# Controller.net
KiCad netlist of a schematic drawn in Altium Designer
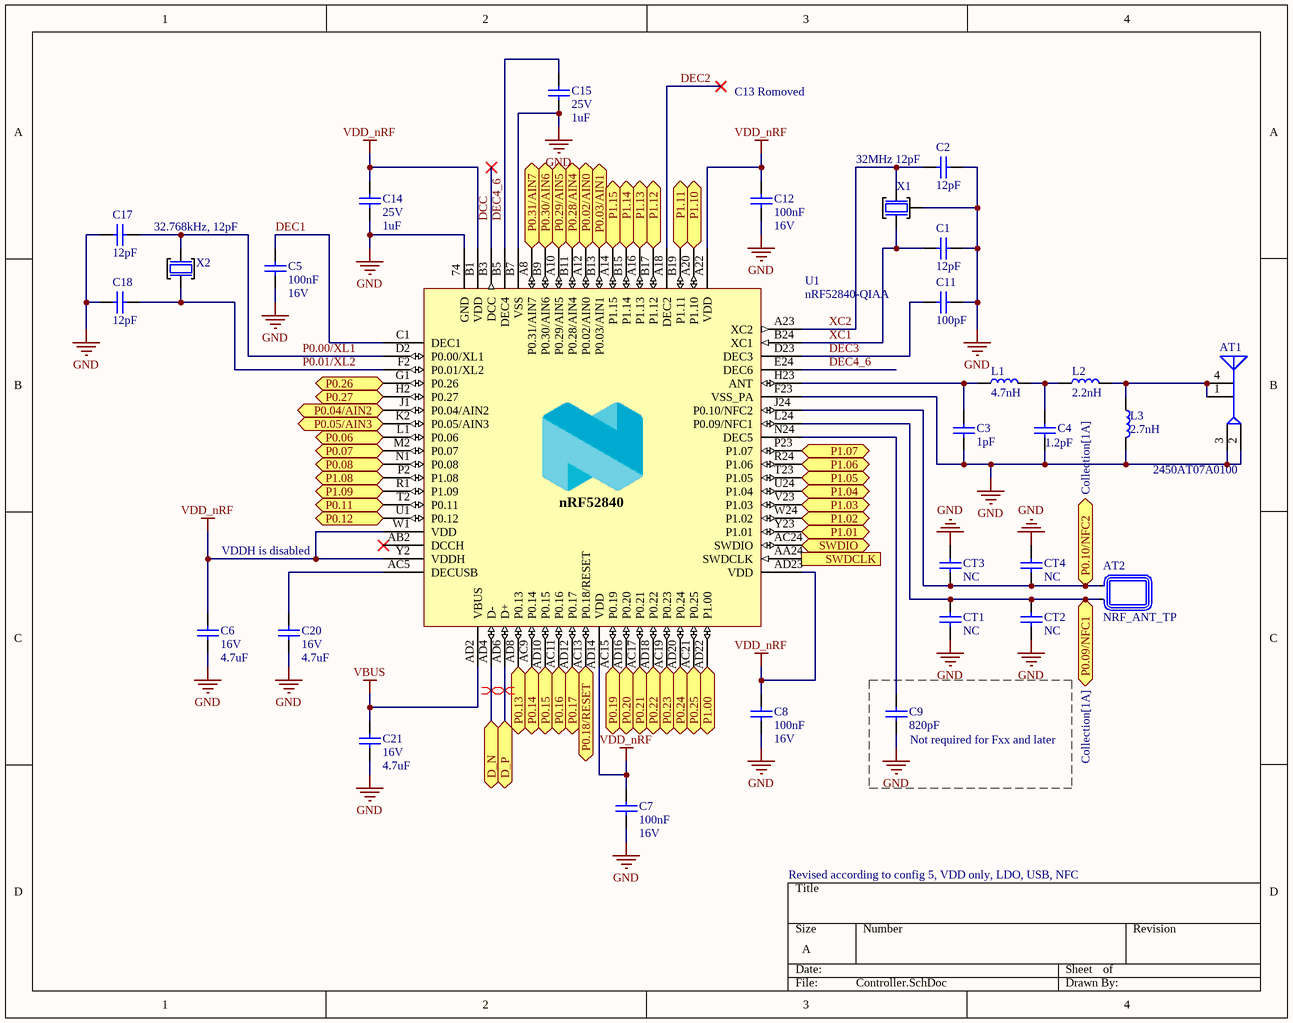
[diagram p0: Controller.SchDoc]

(export (version "E")
  (design (tool "Eeschema 10.0.6"))
  (components
    (comp (ref "AT1")
      (value "2450AT07A0100")
      (footprint "2450AT07A0100-Footprint-1")
      (description "2.4GHz Chip RF Antenna 2.4GHz ~ 2.5GHz 1dBi Solder Surface Mount")
      (libsource (lib "Kirks") (part "2450AT07A0100-Symbol-1"))
    )
    (comp (ref "AT2")
      (value "NRF_ANT_TP")
      (footprint "NRF_ANT_TP-Footprint-1")
      (description "NRF Antenna Testpoint")
      (libsource (lib "Kirks") (part "NRF_ANT_TP-Symbol-1"))
    )
    (comp (ref "C1")
      (value "12pF")
      (footprint "0402_C")
      (description "Chip Capacitor")
      (fields (field (name "VOLTAGE") "50V") (field (name "Comment") "12pF (120) 5% 50V"))
      (libsource (lib "LocalLib") (part "0402 12pF (120) 5% 50V"))
    )
    (comp (ref "C2")
      (value "12pF")
      (footprint "0402_C")
      (description "Chip Capacitor")
      (fields (field (name "VOLTAGE") "50V") (field (name "Comment") "12pF (120) 5% 50V"))
      (libsource (lib "LocalLib") (part "0402 12pF (120) 5% 50V"))
    )
    (comp (ref "C3")
      (value "1pF")
      (footprint "0402_C")
      (description "Chip Capacitor")
      (fields (field (name "VOLTAGE") "50V") (field (name "Comment") "1pF (1R0) 0.25pF 50V"))
      (libsource (lib "LocalLib") (part "0402 1pF (1R0) 0.25pF 50V"))
    )
    (comp (ref "C4")
      (value "1.2pF")
      (footprint "0402_C")
      (description "Chip Capacitor")
      (fields (field (name "VOLTAGE") "50V") (field (name "Comment") "1.2pF (1R2) 50V"))
      (libsource (lib "LocalLib") (part "0402 1.2pF (1R2) 50V"))
    )
    (comp (ref "C5")
      (value "100nF")
      (footprint "0402_C")
      (description "Chip Capacitor")
      (fields (field (name "VOLTAGE") "16V") (field (name "Comment") "100nF (104) 10% 16V"))
      (libsource (lib "LocalLib") (part "0402 100nF (104) 10% 16V"))
    )
    (comp (ref "C6")
      (value "4.7uF")
      (footprint "0603_C")
      (description "Chip Capacitor")
      (fields (field (name "VOLTAGE") "16V") (field (name "Comment") "4.7uF (475) 10% 16V"))
      (libsource (lib "LocalLib") (part "0603 4.7uF (475) 10% 16V"))
    )
    (comp (ref "C7")
      (value "100nF")
      (footprint "0402_C")
      (description "Chip Capacitor")
      (fields (field (name "VOLTAGE") "16V") (field (name "Comment") "100nF (104) 10% 16V"))
      (libsource (lib "LocalLib") (part "0402 100nF (104) 10% 16V"))
    )
    (comp (ref "C8")
      (value "100nF")
      (footprint "0402_C")
      (description "Chip Capacitor")
      (fields (field (name "VOLTAGE") "16V") (field (name "Comment") "100nF (104) 10% 16V"))
      (libsource (lib "LocalLib") (part "0402 100nF (104) 10% 16V"))
    )
    (comp (ref "C9")
      (value "820pF")
      (footprint "0402_C")
      (description "Chip Capacitor")
      (fields (field (name "VOLTAGE") "50V") (field (name "Comment") "820pF (821) 10% 50V"))
      (libsource (lib "LocalLib") (part "0402 820pF (821) 10% 50V"))
    )
    (comp (ref "C11")
      (value "100pF")
      (footprint "0402_C")
      (description "Chip Capacitor")
      (fields (field (name "VOLTAGE") "50V") (field (name "Comment") "100pF (101) 5% 50V"))
      (libsource (lib "LocalLib") (part "0402 100pF (101) 5% 50V"))
    )
    (comp (ref "C12")
      (value "100nF")
      (footprint "0402_C")
      (description "Chip Capacitor")
      (fields (field (name "VOLTAGE") "16V") (field (name "Comment") "100nF (104) 10% 16V"))
      (libsource (lib "LocalLib") (part "0402 100nF (104) 10% 16V"))
    )
    (comp (ref "C14")
      (value "1uF")
      (footprint "0402_C")
      (description "Chip Capacitor")
      (fields (field (name "VOLTAGE") "25V") (field (name "Comment") "1uF (105) 10% 25V"))
      (libsource (lib "LocalLib") (part "0402 1uF (105) 10% 25V"))
    )
    (comp (ref "C15")
      (value "1uF")
      (footprint "0402_C")
      (description "Chip Capacitor")
      (fields (field (name "VOLTAGE") "25V") (field (name "Comment") "1uF (105) 10% 25V"))
      (libsource (lib "LocalLib") (part "0402 1uF (105) 10% 25V"))
    )
    (comp (ref "C17")
      (value "12pF")
      (footprint "0402_C")
      (description "Chip Capacitor")
      (fields (field (name "VOLTAGE") "50V") (field (name "Comment") "12pF (120) 5% 50V"))
      (libsource (lib "LocalLib") (part "0402 12pF (120) 5% 50V"))
    )
    (comp (ref "C18")
      (value "12pF")
      (footprint "0402_C")
      (description "Chip Capacitor")
      (fields (field (name "VOLTAGE") "50V") (field (name "Comment") "12pF (120) 5% 50V"))
      (libsource (lib "LocalLib") (part "0402 12pF (120) 5% 50V"))
    )
    (comp (ref "C20")
      (value "4.7uF")
      (footprint "0603_C")
      (description "Chip Capacitor")
      (fields (field (name "VOLTAGE") "16V") (field (name "Comment") "4.7uF (475) 10% 16V"))
      (libsource (lib "LocalLib") (part "0603 4.7uF (475) 10% 16V"))
    )
    (comp (ref "C21")
      (value "4.7uF")
      (footprint "0603_C")
      (description "Chip Capacitor")
      (fields (field (name "VOLTAGE") "16V") (field (name "Comment") "4.7uF (475) 10% 16V"))
      (libsource (lib "LocalLib") (part "0603 4.7uF (475) 10% 16V"))
    )
    (comp (ref "CT1")
      (value "NC")
      (footprint "0402_C")
      (description "Chip Capacitor Testpoint")
      (libsource (lib "LocalLib") (part "0402 Capacitor Testpoint"))
    )
    (comp (ref "CT2")
      (value "NC")
      (footprint "0402_C")
      (description "Chip Capacitor Testpoint")
      (libsource (lib "LocalLib") (part "0402 Capacitor Testpoint"))
    )
    (comp (ref "CT3")
      (value "NC")
      (footprint "0402_C")
      (description "Chip Capacitor Testpoint")
      (libsource (lib "LocalLib") (part "0402 Capacitor Testpoint"))
    )
    (comp (ref "CT4")
      (value "NC")
      (footprint "0402_C")
      (description "Chip Capacitor Testpoint")
      (libsource (lib "LocalLib") (part "0402 Capacitor Testpoint"))
    )
    (comp (ref "L1")
      (value "4.7nH")
      (footprint "0402_L")
      (description "Chip Inductor")
      (libsource (lib "LocalLib") (part "0402 4.7nH 0.3nH"))
    )
    (comp (ref "L2")
      (value "2.2nH")
      (footprint "0402_L")
      (description "Chip Inductor")
      (libsource (lib "LocalLib") (part "0402 2.2nH"))
    )
    (comp (ref "L3")
      (value "2.7nH")
      (footprint "0402_L")
      (description "Chip Inductor")
      (libsource (lib "LocalLib") (part "0402 2.7nH 0.3nH"))
    )
    (comp (ref "U1")
      (value "nRF52840-QIAA")
      (footprint "AQFN50P700X700X85_HS-74N")
      (description "Multi-protocol Bluetooth Low Energy, IEEE 802.15.4, ANT and 2.4GHz proprietary system-on-chip")
      (libsource (lib "LocalLib") (part "nRF52840-QIAA"))
    )
    (comp (ref "X1")
      (value "32MHz 12pF")
      (footprint "XTAL_2016_4P")
      (description "XTAL SMD 2016, 32MHz, Cl=12pF, Total Tol: ±20ppm")
      (libsource (lib "LocalLib") (part "XTAL_SMD2016_32MHz_12pF"))
    )
    (comp (ref "X2")
      (value "32.768kHz, 12pF")
      (footprint "XTAL_2012_2P")
      (description "32.768kHz 12pF ±20ppm SMD2012-2P  Crystals ROHS")
      (libsource (lib "LocalLib") (part "XTAL_SMD2012_32.768kHz_12pF"))
    )
  )
  (nets
    (net (code "1") (name "/DCC") (class "Default")
      (node (ref "U1") (pin "B3") (pinfunction "DCC_B3") (pintype "output+no_connect"))
    )
    (net (code "2") (name "/DEC1") (class "Default")
      (node (ref "C5") (pin "2") (pinfunction "2_2") (pintype "passive"))
      (node (ref "U1") (pin "C1") (pinfunction "DEC1_C1") (pintype "power_in"))
    )
    (net (code "3") (name "/DEC2") (class "Default")
      (node (ref "U1") (pin "A18") (pinfunction "DEC2_A18") (pintype "power_in+no_connect"))
    )
    (net (code "4") (name "/DEC3") (class "Default")
      (node (ref "C11") (pin "1") (pinfunction "1_1") (pintype "passive"))
      (node (ref "U1") (pin "D23") (pinfunction "DEC3_D23") (pintype "power_in"))
    )
    (net (code "5") (name "/DEC4_6") (class "Default")
      (node (ref "C15") (pin "2") (pinfunction "2_2") (pintype "passive"))
      (node (ref "U1") (pin "B5") (pinfunction "DEC4_B5") (pintype "power_in"))
      (node (ref "U1") (pin "E24") (pinfunction "DEC6_E24") (pintype "power_in"))
    )
    (net (code "6") (name "/D_N") (class "Default")
      (node (ref "U1") (pin "AD4") (pinfunction "D-_AD4") (pintype "bidirectional"))
    )
    (net (code "7") (name "/D_P") (class "Default")
      (node (ref "U1") (pin "AD6") (pinfunction "D+_AD6") (pintype "bidirectional"))
    )
    (net (code "8") (name "/P0.00{slash}XL1") (class "Default")
      (node (ref "C17") (pin "2") (pinfunction "2_2") (pintype "passive"))
      (node (ref "U1") (pin "D2") (pinfunction "P0.00/XL1_D2") (pintype "bidirectional"))
      (node (ref "X2") (pin "2") (pinfunction "OUT_2") (pintype "passive"))
    )
    (net (code "9") (name "/P0.01{slash}XL2") (class "Default")
      (node (ref "C18") (pin "2") (pinfunction "2_2") (pintype "passive"))
      (node (ref "U1") (pin "F2") (pinfunction "P0.01/XL2_F2") (pintype "bidirectional"))
      (node (ref "X2") (pin "1") (pinfunction "IN_1") (pintype "passive"))
    )
    (net (code "10") (name "/P0.02{slash}AIN0") (class "Default")
      (node (ref "U1") (pin "A12") (pinfunction "P0.02/AIN0_A12") (pintype "bidirectional"))
    )
    (net (code "11") (name "/P0.03{slash}AIN1") (class "Default")
      (node (ref "U1") (pin "B13") (pinfunction "P0.03/AIN1_B13") (pintype "bidirectional"))
    )
    (net (code "12") (name "/P0.04{slash}AIN2") (class "Default")
      (node (ref "U1") (pin "J1") (pinfunction "P0.04/AIN2_J1") (pintype "bidirectional"))
    )
    (net (code "13") (name "/P0.05{slash}AIN3") (class "Default")
      (node (ref "U1") (pin "K2") (pinfunction "P0.05/AIN3_K2") (pintype "bidirectional"))
    )
    (net (code "14") (name "/P0.06") (class "Default")
      (node (ref "U1") (pin "L1") (pinfunction "P0.06_L1") (pintype "bidirectional"))
    )
    (net (code "15") (name "/P0.07") (class "Default")
      (node (ref "U1") (pin "M2") (pinfunction "P0.07_M2") (pintype "bidirectional"))
    )
    (net (code "16") (name "/P0.08") (class "Default")
      (node (ref "U1") (pin "N1") (pinfunction "P0.08_N1") (pintype "bidirectional"))
    )
    (net (code "17") (name "/P0.09{slash}NFC1") (class "Default")
      (node (ref "AT2") (pin "2") (pinfunction "2_2") (pintype "passive"))
      (node (ref "CT1") (pin "2") (pinfunction "2_2") (pintype "passive"))
      (node (ref "CT2") (pin "2") (pinfunction "2_2") (pintype "passive"))
      (node (ref "U1") (pin "L24") (pinfunction "P0.09/NFC1_L24") (pintype "bidirectional"))
    )
    (net (code "18") (name "/P0.10{slash}NFC2") (class "Default")
      (node (ref "AT2") (pin "1") (pinfunction "1_1") (pintype "passive"))
      (node (ref "CT3") (pin "1") (pinfunction "1_1") (pintype "passive"))
      (node (ref "CT4") (pin "1") (pinfunction "1_1") (pintype "passive"))
      (node (ref "U1") (pin "J24") (pinfunction "P0.10/NFC2_J24") (pintype "bidirectional"))
    )
    (net (code "19") (name "/P0.11") (class "Default")
      (node (ref "U1") (pin "T2") (pinfunction "P0.11_T2") (pintype "bidirectional"))
    )
    (net (code "20") (name "/P0.12") (class "Default")
      (node (ref "U1") (pin "U1") (pinfunction "P0.12_U1") (pintype "bidirectional"))
    )
    (net (code "21") (name "/P0.13") (class "Default")
      (node (ref "U1") (pin "AD8") (pinfunction "P0.13_AD8") (pintype "bidirectional"))
    )
    (net (code "22") (name "/P0.14") (class "Default")
      (node (ref "U1") (pin "AC9") (pinfunction "P0.14_AC9") (pintype "bidirectional"))
    )
    (net (code "23") (name "/P0.15") (class "Default")
      (node (ref "U1") (pin "AD10") (pinfunction "P0.15_AD10") (pintype "bidirectional"))
    )
    (net (code "24") (name "/P0.16") (class "Default")
      (node (ref "U1") (pin "AC11") (pinfunction "P0.16_AC11") (pintype "bidirectional"))
    )
    (net (code "25") (name "/P0.17") (class "Default")
      (node (ref "U1") (pin "AD12") (pinfunction "P0.17_AD12") (pintype "bidirectional"))
    )
    (net (code "26") (name "/P0.18{slash}RESET") (class "Default")
      (node (ref "U1") (pin "AC13") (pinfunction "P0.18/RESET_AC13") (pintype "bidirectional"))
    )
    (net (code "27") (name "/P0.19") (class "Default")
      (node (ref "U1") (pin "AC15") (pinfunction "P0.19_AC15") (pintype "bidirectional"))
    )
    (net (code "28") (name "/P0.20") (class "Default")
      (node (ref "U1") (pin "AD16") (pinfunction "P0.20_AD16") (pintype "bidirectional"))
    )
    (net (code "29") (name "/P0.21") (class "Default")
      (node (ref "U1") (pin "AC17") (pinfunction "P0.21_AC17") (pintype "bidirectional"))
    )
    (net (code "30") (name "/P0.22") (class "Default")
      (node (ref "U1") (pin "AD18") (pinfunction "P0.22_AD18") (pintype "bidirectional"))
    )
    (net (code "31") (name "/P0.23") (class "Default")
      (node (ref "U1") (pin "AC19") (pinfunction "P0.23_AC19") (pintype "bidirectional"))
    )
    (net (code "32") (name "/P0.24") (class "Default")
      (node (ref "U1") (pin "AD20") (pinfunction "P0.24_AD20") (pintype "bidirectional"))
    )
    (net (code "33") (name "/P0.25") (class "Default")
      (node (ref "U1") (pin "AC21") (pinfunction "P0.25_AC21") (pintype "bidirectional"))
    )
    (net (code "34") (name "/P0.26") (class "Default")
      (node (ref "U1") (pin "G1") (pinfunction "P0.26_G1") (pintype "bidirectional"))
    )
    (net (code "35") (name "/P0.27") (class "Default")
      (node (ref "U1") (pin "H2") (pinfunction "P0.27_H2") (pintype "bidirectional"))
    )
    (net (code "36") (name "/P0.28{slash}AIN4") (class "Default")
      (node (ref "U1") (pin "B11") (pinfunction "P0.28/AIN4_B11") (pintype "bidirectional"))
    )
    (net (code "37") (name "/P0.29{slash}AIN5") (class "Default")
      (node (ref "U1") (pin "A10") (pinfunction "P0.29/AIN5_A10") (pintype "bidirectional"))
    )
    (net (code "38") (name "/P0.30{slash}AIN6") (class "Default")
      (node (ref "U1") (pin "B9") (pinfunction "P0.30/AIN6_B9") (pintype "bidirectional"))
    )
    (net (code "39") (name "/P0.31{slash}AIN7") (class "Default")
      (node (ref "U1") (pin "A8") (pinfunction "P0.31/AIN7_A8") (pintype "bidirectional"))
    )
    (net (code "40") (name "/P1.00") (class "Default")
      (node (ref "U1") (pin "AD22") (pinfunction "P1.00_AD22") (pintype "bidirectional"))
    )
    (net (code "41") (name "/P1.01") (class "Default")
      (node (ref "U1") (pin "Y23") (pinfunction "P1.01_Y23") (pintype "bidirectional"))
    )
    (net (code "42") (name "/P1.02") (class "Default")
      (node (ref "U1") (pin "W24") (pinfunction "P1.02_W24") (pintype "bidirectional"))
    )
    (net (code "43") (name "/P1.03") (class "Default")
      (node (ref "U1") (pin "V23") (pinfunction "P1.03_V23") (pintype "bidirectional"))
    )
    (net (code "44") (name "/P1.04") (class "Default")
      (node (ref "U1") (pin "U24") (pinfunction "P1.04_U24") (pintype "bidirectional"))
    )
    (net (code "45") (name "/P1.05") (class "Default")
      (node (ref "U1") (pin "T23") (pinfunction "P1.05_T23") (pintype "bidirectional"))
    )
    (net (code "46") (name "/P1.06") (class "Default")
      (node (ref "U1") (pin "R24") (pinfunction "P1.06_R24") (pintype "bidirectional"))
    )
    (net (code "47") (name "/P1.07") (class "Default")
      (node (ref "U1") (pin "P23") (pinfunction "P1.07_P23") (pintype "bidirectional"))
    )
    (net (code "48") (name "/P1.08") (class "Default")
      (node (ref "U1") (pin "P2") (pinfunction "P1.08_P2") (pintype "bidirectional"))
    )
    (net (code "49") (name "/P1.09") (class "Default")
      (node (ref "U1") (pin "R1") (pinfunction "P1.09_R1") (pintype "bidirectional"))
    )
    (net (code "50") (name "/P1.10") (class "Default")
      (node (ref "U1") (pin "A20") (pinfunction "P1.10_A20") (pintype "bidirectional"))
    )
    (net (code "51") (name "/P1.11") (class "Default")
      (node (ref "U1") (pin "B19") (pinfunction "P1.11_B19") (pintype "bidirectional"))
    )
    (net (code "52") (name "/P1.12") (class "Default")
      (node (ref "U1") (pin "B17") (pinfunction "P1.12_B17") (pintype "bidirectional"))
    )
    (net (code "53") (name "/P1.13") (class "Default")
      (node (ref "U1") (pin "A16") (pinfunction "P1.13_A16") (pintype "bidirectional"))
    )
    (net (code "54") (name "/P1.14") (class "Default")
      (node (ref "U1") (pin "B15") (pinfunction "P1.14_B15") (pintype "bidirectional"))
    )
    (net (code "55") (name "/P1.15") (class "Default")
      (node (ref "U1") (pin "A14") (pinfunction "P1.15_A14") (pintype "bidirectional"))
    )
    (net (code "56") (name "/SWDCLK") (class "Default")
      (node (ref "U1") (pin "AA24") (pinfunction "SWDCLK_AA24") (pintype "input"))
    )
    (net (code "57") (name "/SWDIO") (class "Default")
      (node (ref "U1") (pin "AC24") (pinfunction "SWDIO_AC24") (pintype "bidirectional"))
    )
    (net (code "58") (name "/XC1") (class "Default")
      (node (ref "C1") (pin "1") (pinfunction "1_1") (pintype "passive"))
      (node (ref "U1") (pin "B24") (pinfunction "XC1_B24") (pintype "input"))
      (node (ref "X1") (pin "1") (pinfunction "IN_1") (pintype "passive"))
    )
    (net (code "59") (name "/XC2") (class "Default")
      (node (ref "C2") (pin "1") (pinfunction "1_1") (pintype "passive"))
      (node (ref "U1") (pin "A23") (pinfunction "XC2_A23") (pintype "output"))
      (node (ref "X1") (pin "3") (pinfunction "OUT_3") (pintype "passive"))
    )
    (net (code "60") (name "GND") (class "Default")
      (node (ref "AT1") (pin "2") (pinfunction "2_2") (pintype "passive"))
      (node (ref "AT1") (pin "3") (pinfunction "3_3") (pintype "passive"))
      (node (ref "C1") (pin "2") (pinfunction "2_2") (pintype "passive"))
      (node (ref "C11") (pin "2") (pinfunction "2_2") (pintype "passive"))
      (node (ref "C12") (pin "1") (pinfunction "1_1") (pintype "passive"))
      (node (ref "C14") (pin "1") (pinfunction "1_1") (pintype "passive"))
      (node (ref "C15") (pin "1") (pinfunction "1_1") (pintype "passive"))
      (node (ref "C17") (pin "1") (pinfunction "1_1") (pintype "passive"))
      (node (ref "C18") (pin "1") (pinfunction "1_1") (pintype "passive"))
      (node (ref "C2") (pin "2") (pinfunction "2_2") (pintype "passive"))
      (node (ref "C20") (pin "1") (pinfunction "1_1") (pintype "passive"))
      (node (ref "C21") (pin "1") (pinfunction "1_1") (pintype "passive"))
      (node (ref "C3") (pin "1") (pinfunction "1_1") (pintype "passive"))
      (node (ref "C4") (pin "1") (pinfunction "1_1") (pintype "passive"))
      (node (ref "C5") (pin "1") (pinfunction "1_1") (pintype "passive"))
      (node (ref "C6") (pin "1") (pinfunction "1_1") (pintype "passive"))
      (node (ref "C7") (pin "1") (pinfunction "1_1") (pintype "passive"))
      (node (ref "C8") (pin "1") (pinfunction "1_1") (pintype "passive"))
      (node (ref "C9") (pin "1") (pinfunction "1_1") (pintype "passive"))
      (node (ref "CT1") (pin "1") (pinfunction "1_1") (pintype "passive"))
      (node (ref "CT2") (pin "1") (pinfunction "1_1") (pintype "passive"))
      (node (ref "CT3") (pin "2") (pinfunction "2_2") (pintype "passive"))
      (node (ref "CT4") (pin "2") (pinfunction "2_2") (pintype "passive"))
      (node (ref "L3") (pin "2") (pinfunction "2_2") (pintype "passive"))
      (node (ref "U1") (pin "74") (pinfunction "GND_74") (pintype "power_in"))
      (node (ref "U1") (pin "B7") (pinfunction "VSS_B7") (pintype "power_in"))
      (node (ref "U1") (pin "F23") (pinfunction "VSS_PA_F23") (pintype "power_in"))
      (node (ref "X1") (pin "2") (pinfunction "GND_2") (pintype "passive"))
    )
    (net (code "61") (name "Net-(AT1-Pad1)") (class "Default")
      (node (ref "AT1") (pin "1") (pinfunction "1_1") (pintype "passive"))
      (node (ref "AT1") (pin "4") (pinfunction "4_4") (pintype "passive"))
      (node (ref "L2") (pin "2") (pinfunction "2_2") (pintype "passive"))
      (node (ref "L3") (pin "1") (pinfunction "1_1") (pintype "passive"))
    )
    (net (code "62") (name "Net-(C4-Pad2)") (class "Default")
      (node (ref "C4") (pin "2") (pinfunction "2_2") (pintype "passive"))
      (node (ref "L1") (pin "2") (pinfunction "2_2") (pintype "passive"))
      (node (ref "L2") (pin "1") (pinfunction "1_1") (pintype "passive"))
    )
    (net (code "63") (name "Net-(U1-ANT)") (class "Default")
      (node (ref "C3") (pin "2") (pinfunction "2_2") (pintype "passive"))
      (node (ref "L1") (pin "1") (pinfunction "1_1") (pintype "passive"))
      (node (ref "U1") (pin "H23") (pinfunction "ANT_H23") (pintype "bidirectional"))
    )
    (net (code "64") (name "Net-(U1-DEC5)") (class "Default")
      (node (ref "C9") (pin "2") (pinfunction "2_2") (pintype "passive"))
      (node (ref "U1") (pin "N24") (pinfunction "DEC5_N24") (pintype "power_in"))
    )
    (net (code "65") (name "Net-(U1-DECUSB)") (class "Default")
      (node (ref "C20") (pin "2") (pinfunction "2_2") (pintype "passive"))
      (node (ref "U1") (pin "AC5") (pinfunction "DECUSB_AC5") (pintype "power_in"))
    )
    (net (code "66") (name "VBUS") (class "Default")
      (node (ref "C21") (pin "2") (pinfunction "2_2") (pintype "passive"))
      (node (ref "U1") (pin "AD2") (pinfunction "VBUS_AD2") (pintype "power_in"))
    )
    (net (code "67") (name "VDD_nRF") (class "Default")
      (node (ref "C12") (pin "2") (pinfunction "2_2") (pintype "passive"))
      (node (ref "C14") (pin "2") (pinfunction "2_2") (pintype "passive"))
      (node (ref "C6") (pin "2") (pinfunction "2_2") (pintype "passive"))
      (node (ref "C7") (pin "2") (pinfunction "2_2") (pintype "passive"))
      (node (ref "C8") (pin "2") (pinfunction "2_2") (pintype "passive"))
      (node (ref "U1") (pin "A22") (pinfunction "VDD_A22") (pintype "power_in"))
      (node (ref "U1") (pin "AD14") (pinfunction "VDD_AD14") (pintype "power_in"))
      (node (ref "U1") (pin "AD23") (pinfunction "VDD_AD23") (pintype "power_in"))
      (node (ref "U1") (pin "B1") (pinfunction "VDD_B1") (pintype "power_in"))
      (node (ref "U1") (pin "W1") (pinfunction "VDD_W1") (pintype "power_in"))
      (node (ref "U1") (pin "Y2") (pinfunction "VDDH_Y2") (pintype "power_in"))
    )
    (net (code "68") (name "unconnected-(U1-DCCH-PadAB2)") (class "Default")
      (node (ref "U1") (pin "AB2") (pinfunction "DCCH_AB2") (pintype "power_in+no_connect"))
    )
  )
)
